# Power_CAN_IO_GPS.net
KiCad netlist of a schematic drawn in Altium Designer
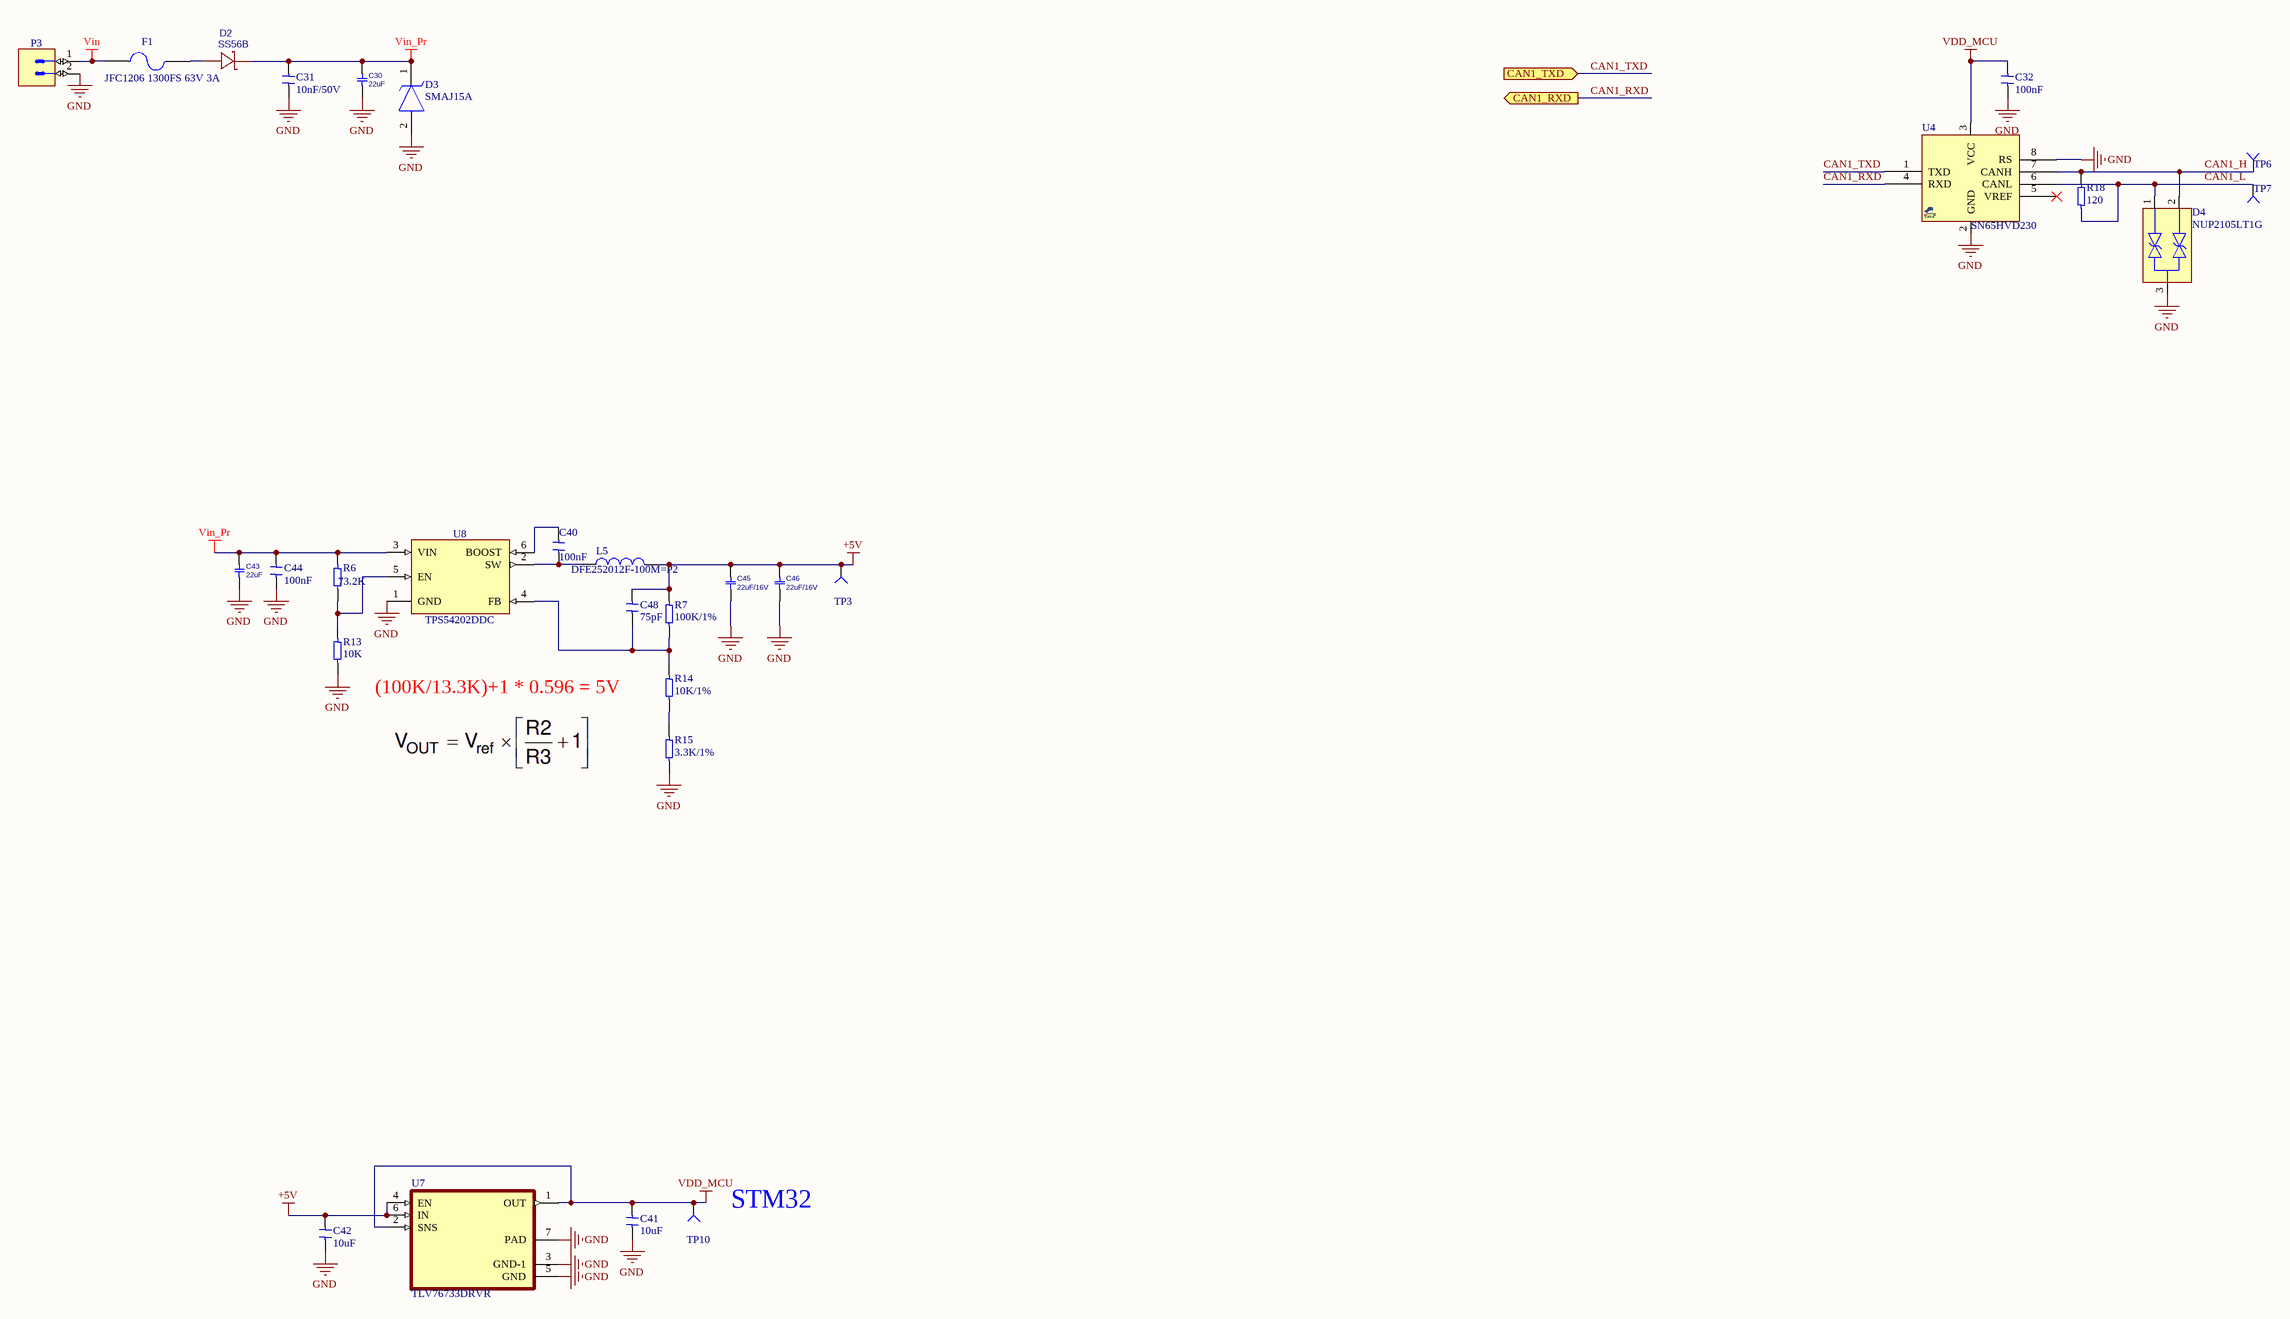
[diagram p0: Power_CAN_IO_GPS.SchDoc]

(export (version "E")
  (design (tool "Eeschema 10.0.6"))
  (components
    (comp (ref "C30")
      (value "22uF")
      (footprint "C1206E")
      (description "CAP, MLCC, X5R 22uF 25V 20% 1206")
      (fields (field (name "MANF_P#") "TMK316BBJ226ML-T") (field (name "MANF") "Taiyo Yuden"))
      (libsource (lib "mlcc_smd_passive") (part "CAP_SMD_MLCC_22u25V"))
    )
    (comp (ref "C31")
      (value "10nF/50V")
      (footprint "C0603E")
      (libsource (lib "Rahimi librery") (part "Capacitor SMD"))
    )
    (comp (ref "C32")
      (value "100nF")
      (footprint "C0603E")
      (libsource (lib "Rahimi librery") (part "Capacitor SMD"))
    )
    (comp (ref "C40")
      (value "100nF")
      (footprint "C0603E")
      (libsource (lib "Rahimi librery") (part "Capacitor SMD"))
    )
    (comp (ref "C41")
      (value "10uF")
      (footprint "C0603E")
      (libsource (lib "Rahimi librery") (part "Capacitor SMD"))
    )
    (comp (ref "C42")
      (value "10uF")
      (footprint "C0603E")
      (libsource (lib "Rahimi librery") (part "Capacitor SMD"))
    )
    (comp (ref "C43")
      (value "22uF")
      (footprint "C1206E")
      (description "CAP, MLCC, X5R 22uF 25V 20% 1206")
      (fields (field (name "MANF_P#") "TMK316BBJ226ML-T") (field (name "MANF") "Taiyo Yuden"))
      (libsource (lib "mlcc_smd_passive") (part "CAP_SMD_MLCC_22u25V"))
    )
    (comp (ref "C44")
      (value "100nF")
      (footprint "C0603E")
      (libsource (lib "Rahimi librery") (part "Capacitor SMD"))
    )
    (comp (ref "C45")
      (value "22uF/16V")
      (footprint "C1206E")
      (description "CAP, MLCC, X5R 22uF 25V 20% 1206")
      (fields (field (name "MANF_P#") "TMK316BBJ226ML-T") (field (name "MANF") "Taiyo Yuden"))
      (libsource (lib "mlcc_smd_passive") (part "CAP_SMD_MLCC_22u25V"))
    )
    (comp (ref "C46")
      (value "22uF/16V")
      (footprint "C1206E")
      (description "CAP, MLCC, X5R 22uF 25V 20% 1206")
      (fields (field (name "MANF_P#") "TMK316BBJ226ML-T") (field (name "MANF") "Taiyo Yuden"))
      (libsource (lib "mlcc_smd_passive") (part "CAP_SMD_MLCC_22u25V"))
    )
    (comp (ref "C48")
      (value "75pF")
      (footprint "C0603E")
      (libsource (lib "Rahimi librery") (part "Capacitor SMD"))
    )
    (comp (ref "D2")
      (value "SS56B")
      (footprint "SMB_L4.6-W3.6-LS5.3-RD")
      (description "40V 5A Schottky Rectifier")
      (fields
        (field (name "MANUFACTURER") "LGE(鲁光)")
        (field (name "MANUFACTURER PART") "SS54")
        (field (name "CONTRIBUTOR") "LCSC")
      )
      (libsource (lib "altium-import") (part "root_2_SS54C_"))
    )
    (comp (ref "D3")
      (value "SMAJ15A")
      (footprint "DIOM5026X229N")
      (description "TVS Diode (Uni-directional)")
      (fields
        (field (name "MANUFACTURER_PART_NUMBER") "SMAJ24A")
        (field (name "MOUSER PART NUMBER") "576-SMAJ24A")
      )
      (libsource (lib "*") (part "SMAJ24A"))
    )
    (comp (ref "D4")
      (value "NUP2105LT1G")
      (footprint "SOT95P237X111-3N")
      (description "Dual Bi-Directional TVS Diode 350W 3-Pin SOT-23 ¦ ON Semiconductor NUP2105LT1G")
      (fields (field (name "MF") "ON Semiconductor"))
      (libsource (lib "NUP2105LT1G") (part "NUP2105LT1G"))
    )
    (comp (ref "F1")
      (value "JFC1206 1300FS 63V 3A")
      (footprint "1206 FUSE")
      (description "Fuse Type Fast Acting with 63V, 3A, 1206")
      (fields (field (name "DESIGNER") "Abbas Basereh"))
      (libsource (lib "altium-import") (part "root_0_Fuse SMD1206_"))
    )
    (comp (ref "L5")
      (value "DFE252012F-100M=P2")
      (footprint "INDC2520X120N")
      (description "Inductor with Inductance: 10uH Tol. +/-20%, Package: 1008 (2520)")
      (fields (field (name "MF") "Murata Electronics") (field (name "DIGI-KEY_PART_NUMBER") "490-13050-1-ND"))
      (libsource (lib "DFE252012F-100M_P2") (part "DFE252012F-100M=P2"))
    )
    (comp (ref "P3")
      (value "KF2EDGV+K-3.81-2P")
      (footprint "PHOENIX_1803426")
      (description "Connector 2 Male")
      (fields
        (field (name "PART NUMBER") "PHOENIX_1803426")
        (field (name "MANUFACTURER") "PHOENIX CONTACT")
        (field (name "AUTHOR") "CERN DEM JLC")
      )
      (libsource (lib "Connectors") (part "Connector 2 Male"))
    )
    (comp (ref "R6")
      (value "73.2K")
      (footprint "R0603E")
      (libsource (lib "Rahimi librery") (part "Resistor SMD"))
    )
    (comp (ref "R7")
      (value "100K/1%")
      (footprint "R0603E")
      (libsource (lib "Rahimi librery") (part "Resistor SMD"))
    )
    (comp (ref "R13")
      (value "10K")
      (footprint "R0603E")
      (libsource (lib "Rahimi librery") (part "Resistor SMD"))
    )
    (comp (ref "R14")
      (value "10K/1%")
      (footprint "R0603E")
      (libsource (lib "Rahimi librery") (part "Resistor SMD"))
    )
    (comp (ref "R15")
      (value "3.3K/1%")
      (footprint "R0603E")
      (libsource (lib "Rahimi librery") (part "Resistor SMD"))
    )
    (comp (ref "R18")
      (value "120")
      (footprint "R0603E")
      (libsource (lib "Rahimi librery") (part "Resistor SMD"))
    )
    (comp (ref "TP3")
      (value "TEST POINT")
      (footprint "TEST_POINT")
      (libsource (lib "Tracker_MAIN_V1.01") (part "TEST POINT"))
    )
    (comp (ref "TP6")
      (value "TEST POINT")
      (footprint "TEST_POINT")
      (libsource (lib "Tracker_MAIN_V1.01") (part "TEST POINT"))
    )
    (comp (ref "TP7")
      (value "TEST POINT")
      (footprint "TEST_POINT")
      (libsource (lib "Tracker_MAIN_V1.01") (part "TEST POINT"))
    )
    (comp (ref "TP10")
      (value "TEST POINT")
      (footprint "TEST_POINT")
      (libsource (lib "Tracker_MAIN_V1.01") (part "TEST POINT"))
    )
    (comp (ref "U4")
      (value "SN65HVD230")
      (footprint "SO_8")
      (description "CAN,  Transceivers, 3.3V (VDD)")
      (fields (field (name "MANF") "Texas Instruments") (field (name "MANF_P#") "SN65HVD230D, SN65HVD230QD"))
      (libsource (lib "can_phy") (part "SN65HVD230_SOP8"))
    )
    (comp (ref "U7")
      (value "TLV76733DRVR")
      (footprint "SON65P200X200X80-7N")
      (description "Adjustable- and fixed-output, 1-A, 16-V, positive-voltage low-dropout (LDO) linear regulator")
      (fields (field (name "MF") "Texas Instruments"))
      (libsource (lib "NewSpeedRadar_Board") (part "TLV76733DRVR"))
    )
    (comp (ref "U8")
      (value "TPS54202DDC")
      (footprint "SOT95P280X100-6N")
      (description "4.5V to 28V Input, 2-A Output, EMI Friendly\r\nSynchronous Step Down Converter")
      (fields (field (name "MANUFACTURER") "TEXAS INSTRUMENTS") (field (name "AUTHOR") "CERN DEM HF"))
      (libsource (lib "ICs And Semiconductors") (part "TPS54202"))
    )
  )
  (nets
    (net (code "1") (name "+5V") (class "Default")
      (node (ref "C42") (pin "2") (pintype "passive"))
      (node (ref "C45") (pin "2") (pinfunction "2_2") (pintype "passive"))
      (node (ref "C46") (pin "2") (pinfunction "2_2") (pintype "passive"))
      (node (ref "C48") (pin "2") (pintype "passive"))
      (node (ref "L5") (pin "2") (pinfunction "2_2") (pintype "passive"))
      (node (ref "R7") (pin "1") (pintype "passive"))
      (node (ref "TP3") (pin "1") (pinfunction "TP_1") (pintype "passive"))
      (node (ref "U7") (pin "4") (pinfunction "EN_4") (pintype "input"))
      (node (ref "U7") (pin "6") (pinfunction "IN_6") (pintype "input"))
    )
    (net (code "2") (name "/CAN1_H") (class "Default")
      (node (ref "D4") (pin "2") (pinfunction "2_2") (pintype "passive"))
      (node (ref "R18") (pin "2") (pintype "passive"))
      (node (ref "TP6") (pin "1") (pinfunction "TP_1") (pintype "passive"))
      (node (ref "U4") (pin "7") (pinfunction "CANH_7") (pintype "passive"))
    )
    (net (code "3") (name "/CAN1_L") (class "Default")
      (node (ref "D4") (pin "1") (pinfunction "1_1") (pintype "passive"))
      (node (ref "R18") (pin "1") (pintype "passive"))
      (node (ref "TP7") (pin "1") (pinfunction "TP_1") (pintype "passive"))
      (node (ref "U4") (pin "6") (pinfunction "CANL_6") (pintype "passive"))
    )
    (net (code "4") (name "/CAN1_RXD") (class "Default")
      (node (ref "U4") (pin "4") (pinfunction "RXD_4") (pintype "passive"))
    )
    (net (code "5") (name "/CAN1_TXD") (class "Default")
      (node (ref "U4") (pin "1") (pinfunction "TXD_1") (pintype "passive"))
    )
    (net (code "6") (name "GND") (class "Default")
      (node (ref "C30") (pin "1") (pinfunction "1_1") (pintype "passive"))
      (node (ref "C31") (pin "1") (pintype "passive"))
      (node (ref "C32") (pin "1") (pintype "passive"))
      (node (ref "C41") (pin "1") (pintype "passive"))
      (node (ref "C42") (pin "1") (pintype "passive"))
      (node (ref "C43") (pin "1") (pinfunction "1_1") (pintype "passive"))
      (node (ref "C44") (pin "1") (pintype "passive"))
      (node (ref "C45") (pin "1") (pinfunction "1_1") (pintype "passive"))
      (node (ref "C46") (pin "1") (pinfunction "1_1") (pintype "passive"))
      (node (ref "D3") (pin "2") (pinfunction "A_2") (pintype "passive"))
      (node (ref "D4") (pin "3") (pinfunction "3_3") (pintype "passive"))
      (node (ref "P3") (pin "2") (pinfunction "2_2") (pintype "bidirectional"))
      (node (ref "R13") (pin "2") (pintype "passive"))
      (node (ref "R15") (pin "2") (pintype "passive"))
      (node (ref "U4") (pin "2") (pinfunction "GND_2") (pintype "passive"))
      (node (ref "U4") (pin "8") (pinfunction "RS_8") (pintype "passive"))
      (node (ref "U7") (pin "3") (pinfunction "GND-1_3") (pintype "power_in"))
      (node (ref "U7") (pin "5") (pinfunction "GND_5") (pintype "power_in"))
      (node (ref "U7") (pin "7") (pinfunction "PAD_7") (pintype "power_in"))
      (node (ref "U8") (pin "1") (pinfunction "GND_1") (pintype "power_in"))
    )
    (net (code "7") (name "Net-(D2-A)") (class "Default")
      (node (ref "D2") (pin "2") (pinfunction "A_2") (pintype "passive"))
      (node (ref "F1") (pin "2") (pinfunction "2_2") (pintype "passive"))
    )
    (net (code "8") (name "Net-(R14-Pad2)") (class "Default")
      (node (ref "R14") (pin "2") (pintype "passive"))
      (node (ref "R15") (pin "1") (pintype "passive"))
    )
    (net (code "9") (name "Net-(U8-BOOST)") (class "Default")
      (node (ref "C40") (pin "1") (pintype "passive"))
      (node (ref "U8") (pin "6") (pinfunction "BOOST_6") (pintype "input"))
    )
    (net (code "10") (name "Net-(U8-EN)") (class "Default")
      (node (ref "R13") (pin "1") (pintype "passive"))
      (node (ref "R6") (pin "2") (pintype "passive"))
      (node (ref "U8") (pin "5") (pinfunction "EN_5") (pintype "input"))
    )
    (net (code "11") (name "Net-(U8-FB)") (class "Default")
      (node (ref "C48") (pin "1") (pintype "passive"))
      (node (ref "R14") (pin "1") (pintype "passive"))
      (node (ref "R7") (pin "2") (pintype "passive"))
      (node (ref "U8") (pin "4") (pinfunction "FB_4") (pintype "input"))
    )
    (net (code "12") (name "Net-(U8-SW)") (class "Default")
      (node (ref "C40") (pin "2") (pintype "passive"))
      (node (ref "L5") (pin "1") (pinfunction "1_1") (pintype "passive"))
      (node (ref "U8") (pin "2") (pinfunction "SW_2") (pintype "output"))
    )
    (net (code "13") (name "VDD_MCU") (class "Default")
      (node (ref "C32") (pin "2") (pintype "passive"))
      (node (ref "C41") (pin "2") (pintype "passive"))
      (node (ref "TP10") (pin "1") (pinfunction "TP_1") (pintype "passive"))
      (node (ref "U4") (pin "3") (pinfunction "VCC_3") (pintype "passive"))
      (node (ref "U7") (pin "1") (pinfunction "OUT_1") (pintype "output"))
      (node (ref "U7") (pin "2") (pinfunction "SNS_2") (pintype "input"))
    )
    (net (code "14") (name "Vin") (class "Default")
      (node (ref "F1") (pin "1") (pinfunction "1_1") (pintype "passive"))
      (node (ref "P3") (pin "1") (pinfunction "1_1") (pintype "bidirectional"))
    )
    (net (code "15") (name "Vin_Pr") (class "Default")
      (node (ref "C30") (pin "2") (pinfunction "2_2") (pintype "passive"))
      (node (ref "C31") (pin "2") (pintype "passive"))
      (node (ref "C43") (pin "2") (pinfunction "2_2") (pintype "passive"))
      (node (ref "C44") (pin "2") (pintype "passive"))
      (node (ref "D2") (pin "1") (pinfunction "K_1") (pintype "passive"))
      (node (ref "D3") (pin "1") (pinfunction "K_1") (pintype "passive"))
      (node (ref "R6") (pin "1") (pintype "passive"))
      (node (ref "U8") (pin "3") (pinfunction "VIN_3") (pintype "input"))
    )
    (net (code "16") (name "unconnected-(U4-VREF-Pad5)") (class "Default")
      (node (ref "U4") (pin "5") (pinfunction "VREF_5") (pintype "passive+no_connect"))
    )
  )
)
